# SensorShield.net
KiCad netlist of a schematic drawn in Altium Designer
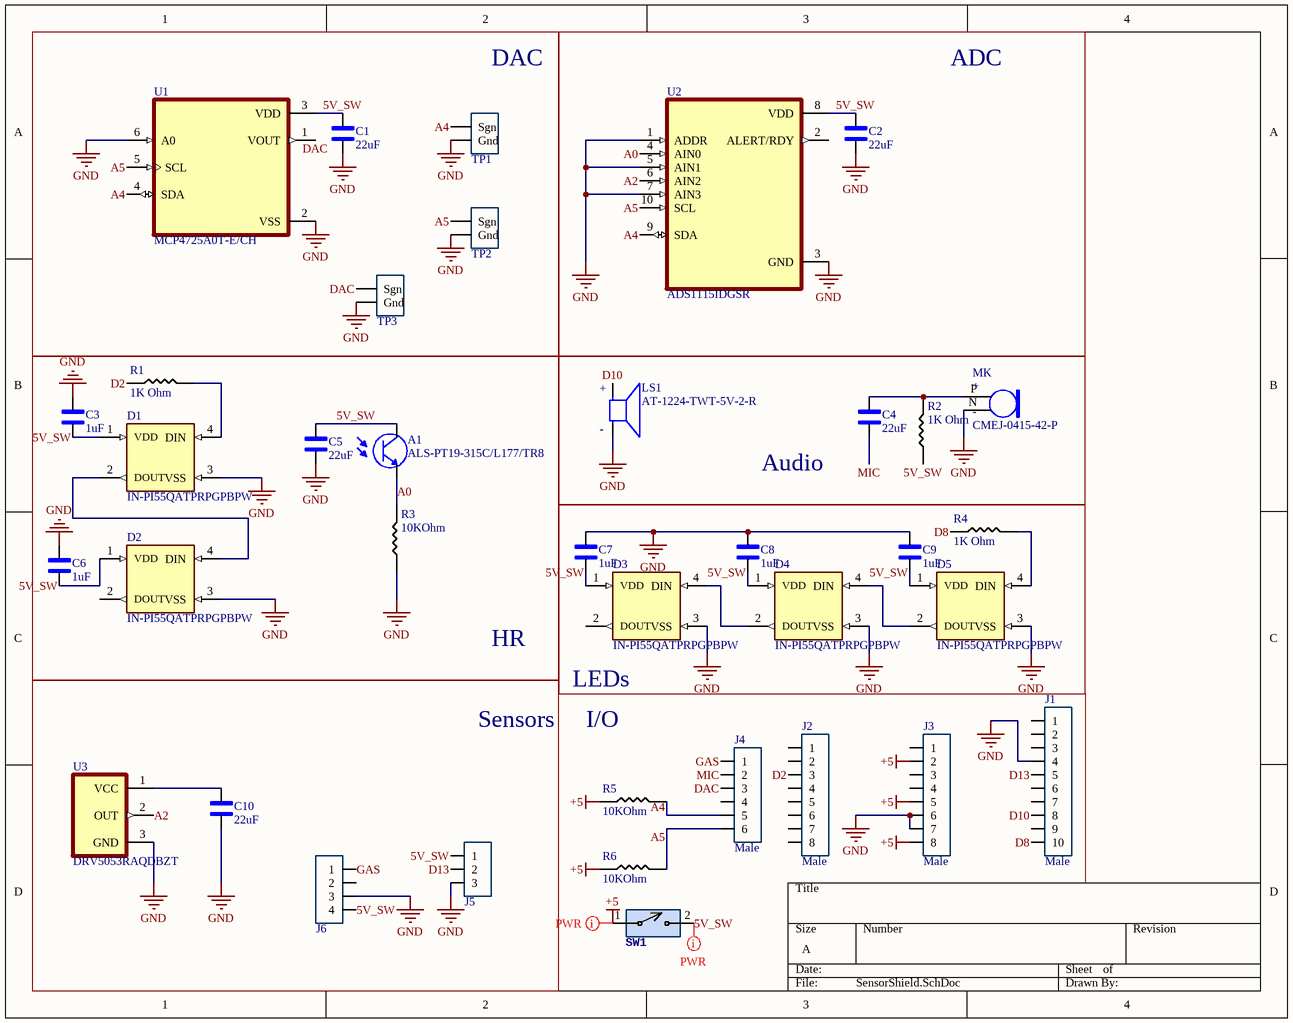
[diagram p0: SensorShield.SchDoc]

(export (version "E")
  (design (tool "Eeschema 10.0.6"))
  (components
    (comp (ref "A1")
      (value "ALS-PT19-315C/L177/TR8")
      (footprint "XDCR_ALS-PT19-315C/L177/TR8")
      (description "Phototransistors 630nm 2-SMD, No Lead")
      (fields (field (name "MF") "Everlight"))
      (libsource (lib "SensorShield") (part "ALS-PT19-315C/L177/TR8"))
    )
    (comp (ref "C1")
      (value "22uF")
      (footprint "1206_Passive_Capacitor")
      (description "22µF ±20% 16V Ceramic Capacitor X5R 1206 (3216 Metric)")
      (fields (field (name "DIGIKEY PART") "1276-2728-1-ND") (field (name "MFR PART #") "CL31A226KPHNNNE"))
      (libsource (lib "ECEN5730Lib_Manual_2021_08") (part "C_22uF_1206"))
    )
    (comp (ref "C2")
      (value "22uF")
      (footprint "1206_Passive_Capacitor")
      (description "22µF ±20% 16V Ceramic Capacitor X5R 1206 (3216 Metric)")
      (fields (field (name "DIGIKEY PART") "1276-2728-1-ND") (field (name "MFR PART #") "CL31A226KPHNNNE"))
      (libsource (lib "ECEN5730Lib_Manual_2021_08") (part "C_22uF_1206"))
    )
    (comp (ref "C3")
      (value "1uF")
      (footprint "1206_Passive_Capacitor")
      (description "1µF ±20% 16V Ceramic Capacitor X7R 1206 (3216 Metric)")
      (fields (field (name "DIGIKEY PART") "399-8150-1-ND") (field (name "MFR PART #") "CL31B105KBHNNNE"))
      (libsource (lib "ECEN5730Lib_Manual_2021_08") (part "C_1uF_1206"))
    )
    (comp (ref "C4")
      (value "22uF")
      (footprint "1206_Passive_Capacitor")
      (description "22µF ±20% 16V Ceramic Capacitor X5R 1206 (3216 Metric)")
      (fields (field (name "DIGIKEY PART") "1276-2728-1-ND") (field (name "MFR PART #") "CL31A226KPHNNNE"))
      (libsource (lib "ECEN5730Lib_Manual_2021_08") (part "C_22uF_1206"))
    )
    (comp (ref "C5")
      (value "22uF")
      (footprint "1206_Passive_Capacitor")
      (description "22µF ±20% 16V Ceramic Capacitor X5R 1206 (3216 Metric)")
      (fields (field (name "DIGIKEY PART") "1276-2728-1-ND") (field (name "MFR PART #") "CL31A226KPHNNNE"))
      (libsource (lib "ECEN5730Lib_Manual_2021_08") (part "C_22uF_1206"))
    )
    (comp (ref "C6")
      (value "1uF")
      (footprint "1206_Passive_Capacitor")
      (description "1µF ±20% 16V Ceramic Capacitor X7R 1206 (3216 Metric)")
      (fields (field (name "DIGIKEY PART") "399-8150-1-ND") (field (name "MFR PART #") "CL31B105KBHNNNE"))
      (libsource (lib "ECEN5730Lib_Manual_2021_08") (part "C_1uF_1206"))
    )
    (comp (ref "C7")
      (value "1uF")
      (footprint "1206_Passive_Capacitor")
      (description "1µF ±20% 16V Ceramic Capacitor X7R 1206 (3216 Metric)")
      (fields (field (name "DIGIKEY PART") "399-8150-1-ND") (field (name "MFR PART #") "CL31B105KBHNNNE"))
      (libsource (lib "ECEN5730Lib_Manual_2021_08") (part "C_1uF_1206"))
    )
    (comp (ref "C8")
      (value "1uF")
      (footprint "1206_Passive_Capacitor")
      (description "1µF ±20% 16V Ceramic Capacitor X7R 1206 (3216 Metric)")
      (fields (field (name "DIGIKEY PART") "399-8150-1-ND") (field (name "MFR PART #") "CL31B105KBHNNNE"))
      (libsource (lib "ECEN5730Lib_Manual_2021_08") (part "C_1uF_1206"))
    )
    (comp (ref "C9")
      (value "1uF")
      (footprint "1206_Passive_Capacitor")
      (description "1µF ±20% 16V Ceramic Capacitor X7R 1206 (3216 Metric)")
      (fields (field (name "DIGIKEY PART") "399-8150-1-ND") (field (name "MFR PART #") "CL31B105KBHNNNE"))
      (libsource (lib "ECEN5730Lib_Manual_2021_08") (part "C_1uF_1206"))
    )
    (comp (ref "C10")
      (value "22uF")
      (footprint "1206_Passive_Capacitor")
      (description "22µF ±20% 16V Ceramic Capacitor X5R 1206 (3216 Metric)")
      (fields (field (name "DIGIKEY PART") "1276-2728-1-ND") (field (name "MFR PART #") "CL31A226KPHNNNE"))
      (libsource (lib "ECEN5730Lib_Manual_2021_08") (part "C_22uF_1206"))
    )
    (comp (ref "D1")
      (value "IN-PI55QATPRPGPBPW")
      (footprint "SERIAL_LED")
      (description "Digital Series Cascade LED")
      (libsource (lib "ECEN5730Lib_Manual_2021_08") (part "LED_Smart_5050"))
    )
    (comp (ref "D2")
      (value "IN-PI55QATPRPGPBPW")
      (footprint "SERIAL_LED")
      (description "Digital Series Cascade LED")
      (libsource (lib "ECEN5730Lib_Manual_2021_08") (part "LED_Smart_5050"))
    )
    (comp (ref "D3")
      (value "IN-PI55QATPRPGPBPW")
      (footprint "SERIAL_LED")
      (description "Digital Series Cascade LED")
      (libsource (lib "ECEN5730Lib_Manual_2021_08") (part "LED_Smart_5050"))
    )
    (comp (ref "D4")
      (value "IN-PI55QATPRPGPBPW")
      (footprint "SERIAL_LED")
      (description "Digital Series Cascade LED")
      (libsource (lib "ECEN5730Lib_Manual_2021_08") (part "LED_Smart_5050"))
    )
    (comp (ref "D5")
      (value "IN-PI55QATPRPGPBPW")
      (footprint "SERIAL_LED")
      (description "Digital Series Cascade LED")
      (libsource (lib "ECEN5730Lib_Manual_2021_08") (part "LED_Smart_5050"))
    )
    (comp (ref "J1")
      (value "Male")
      (footprint "10_PIN_100MIL")
      (description "10 Position Header Connector 0.100\" (2.54mm) Through Hole Tin")
      (fields (field (name "DIGIKEY PART") "S7008-ND") (field (name "LCSC PART#") "DNP"))
      (libsource (lib "ECEN5730Lib_Manual_2021_08") (part "JM_10_PIN_MALE"))
    )
    (comp (ref "J2")
      (value "Male")
      (footprint "8_PIN_100MIL")
      (description "8 Position Header Connector 0.100\" (2.54mm) Through Hole Tin")
      (fields (field (name "DIGIKEY PART") "S7006-ND") (field (name "LCSC PART#") "DNP"))
      (libsource (lib "ECEN5730Lib_Manual_2021_08") (part "JM_8_PIN_MALE"))
    )
    (comp (ref "J3")
      (value "Male")
      (footprint "8_PIN_100MIL")
      (description "8 Position Header Connector 0.100\" (2.54mm) Through Hole Tin")
      (fields (field (name "DIGIKEY PART") "S7006-ND") (field (name "LCSC PART#") "DNP"))
      (libsource (lib "ECEN5730Lib_Manual_2021_08") (part "JM_8_PIN_MALE"))
    )
    (comp (ref "J4")
      (value "Male")
      (footprint "6_PIN_100MIL")
      (description "6 Position Header Connector 0.100\" (2.54mm) Through Hole Tin")
      (fields (field (name "DIGIKEY PART") "S7004-ND") (field (name "LCSC PART#") "DNP"))
      (libsource (lib "ECEN5730Lib_Manual_2021_08") (part "JM_6_PIN_MALE"))
    )
    (comp (ref "J5")
      (value "J_3_PIN_HEADER")
      (footprint "3_PIN_100mil")
      (description "3 Position Header Connector 0.100\" (2.54mm) Through Hole Tin")
      (libsource (lib "ECEN5730Lib_Manual_2021_08") (part "J_3_PIN_HEADER"))
    )
    (comp (ref "J6")
      (value "J_4_PIN_HEADER")
      (footprint "4_PIN_100MIL")
      (description "4 Position Header Connector 0.100\" (2.54mm) Through Hole Tin")
      (libsource (lib "ECEN5730Lib_Manual_2021_08") (part "J_4_PIN_HEADER"))
    )
    (comp (ref "LS1")
      (value "AT-1224-TWT-5V-2-R")
      (footprint "XDCR_AT-1224-TWT-5V-2-R")
      (description "AUDIO TRANSDUCER 5 VP-P 87 DB 2400 HZ")
      (fields (field (name "MF") "PUI Audio,"))
      (libsource (lib "SensorShield") (part "AT-1224-TWT-5V-2-R"))
    )
    (comp (ref "MK")
      (value "CMEJ-0415-42-P")
      (footprint "MIC_CMEJ-0415-42-P")
      (fields (field (name "MF") "CUI Devices") (field (name "DIGI-KEY_PART_NUMBER") "102-6542-ND"))
      (libsource (lib "SensorShield") (part "CMEJ-0415-42-P"))
    )
    (comp (ref "R1")
      (value "1K Ohm")
      (footprint "1206_Passive_Resitor")
      (description "1 kOhms ±1% 0.5W, 1/2W Chip Resistor 1206 (3216 Metric) Anti-Sulfur, Moisture Resistant Thin Film")
      (fields
        (field (name "DIGIKEY PART") "RNCP1206FTD1K00CT-ND")
        (field (name "MFR PART #") "1206W4F1001T5")
      )
      (libsource (lib "ECEN5730Lib_Manual_2021_08") (part "R_1K_1206"))
    )
    (comp (ref "R2")
      (value "1K Ohm")
      (footprint "1206_Passive_Resitor")
      (description "1 kOhms ±1% 0.5W, 1/2W Chip Resistor 1206 (3216 Metric) Anti-Sulfur, Moisture Resistant Thin Film")
      (fields
        (field (name "DIGIKEY PART") "RNCP1206FTD1K00CT-ND")
        (field (name "MFR PART #") "1206W4F1001T5")
      )
      (libsource (lib "ECEN5730Lib_Manual_2021_08") (part "R_1K_1206"))
    )
    (comp (ref "R3")
      (value "10KOhm")
      (footprint "1206_Passive_Resitor")
      (description "10 kOhms ±5% 0.25W, 1/4W Chip Resistor 1206 (3216 Metric) Automotive AEC-Q200 Thick Film")
      (fields (field (name "DIGIKEY PART") "RMCF1206JT300RCT-ND") (field (name "Comment") "10k"))
      (libsource (lib "ECEN5730Lib_Manual_2021_08") (part "R_10KOhm_1206"))
    )
    (comp (ref "R4")
      (value "1K Ohm")
      (footprint "1206_Passive_Resitor")
      (description "1 kOhms ±1% 0.5W, 1/2W Chip Resistor 1206 (3216 Metric) Anti-Sulfur, Moisture Resistant Thin Film")
      (fields
        (field (name "DIGIKEY PART") "RNCP1206FTD1K00CT-ND")
        (field (name "MFR PART #") "1206W4F1001T5")
      )
      (libsource (lib "ECEN5730Lib_Manual_2021_08") (part "R_1K_1206"))
    )
    (comp (ref "R5")
      (value "10KOhm")
      (footprint "1206_Passive_Resitor")
      (description "10 kOhms ±5% 0.25W, 1/4W Chip Resistor 1206 (3216 Metric) Automotive AEC-Q200 Thick Film")
      (fields (field (name "DIGIKEY PART") "RMCF1206JT300RCT-ND") (field (name "Comment") "10k"))
      (libsource (lib "ECEN5730Lib_Manual_2021_08") (part "R_10KOhm_1206"))
    )
    (comp (ref "R6")
      (value "10KOhm")
      (footprint "1206_Passive_Resitor")
      (description "10 kOhms ±5% 0.25W, 1/4W Chip Resistor 1206 (3216 Metric) Automotive AEC-Q200 Thick Film")
      (fields (field (name "DIGIKEY PART") "RMCF1206JT300RCT-ND") (field (name "Comment") "10k"))
      (libsource (lib "ECEN5730Lib_Manual_2021_08") (part "R_10KOhm_1206"))
    )
    (comp (ref "SW1")
      (value "SW_2Pin_100mil_Switch")
      (footprint "2Pin-Header-Conn")
      (description "2Pin Header")
      (fields (field (name "LCSC PART#") "C124375"))
      (libsource (lib "ECEN5730Lib_JLC_2021_08") (part "SW_2Pin_100mil_Switch"))
    )
    (comp (ref "TP1")
      (value "10x Probe TP")
      (footprint "TP10x_Probe")
      (description "Test Point 300 mil centers")
      (libsource (lib "ECEN5730Lib_Manual_2021_08") (part "TP_10x_Probe"))
    )
    (comp (ref "TP2")
      (value "10x Probe TP")
      (footprint "TP10x_Probe")
      (description "Test Point 300 mil centers")
      (libsource (lib "ECEN5730Lib_Manual_2021_08") (part "TP_10x_Probe"))
    )
    (comp (ref "TP3")
      (value "10x Probe TP")
      (footprint "TP10x_Probe")
      (description "Test Point 300 mil centers")
      (libsource (lib "ECEN5730Lib_Manual_2021_08") (part "TP_10x_Probe"))
    )
    (comp (ref "U1")
      (value "MCP4725A0T-E/CH")
      (footprint "SOT95P270X145-6N")
      (description "12 Bit Digital to Analog Converter 1 SOT-23-6")
      (fields (field (name "MF") "Microchip"))
      (libsource (lib "SensorShield") (part "MCP4725A0T-E/CH"))
    )
    (comp (ref "U2")
      (value "ADS1115IDGSR")
      (footprint "SOP50P490X110-10N")
      (fields
        (field (name "MF") "Texas Instruments")
        (field (name "BUYPART") "https://www.snapeda.com/parts/ADS1115IDGSR/Texas%20Instruments/view-part/45903/?ref=eda")
      )
      (libsource (lib "SensorShield") (part "ADS1115IDGSR"))
    )
    (comp (ref "U3")
      (value "DRV5053RAQDBZT")
      (footprint "SOT95P237X112-3N")
      (description "SENSOR LINEAR ANALOG SOT23-3")
      (libsource (lib "SensorShield") (part "DRV5053RAQDBZT"))
    )
  )
  (nets
    (net (code "1") (name "+5") (class "Default")
      (node (ref "J3") (pin "2") (pinfunction "2_2") (pintype "passive"))
      (node (ref "J3") (pin "5") (pinfunction "5_5") (pintype "passive"))
      (node (ref "J3") (pin "8") (pinfunction "8_8") (pintype "passive"))
      (node (ref "R5") (pin "1") (pinfunction "1_1") (pintype "passive"))
      (node (ref "R6") (pin "1") (pinfunction "1_1") (pintype "passive"))
      (node (ref "SW1") (pin "1") (pinfunction "1_1") (pintype "passive"))
    )
    (net (code "2") (name "/5V_SW") (class "Default")
      (node (ref "A1") (pin "1") (pinfunction "C_1") (pintype "passive"))
      (node (ref "C1") (pin "2") (pinfunction "2_2") (pintype "passive"))
      (node (ref "C2") (pin "2") (pinfunction "2_2") (pintype "passive"))
      (node (ref "C3") (pin "1") (pinfunction "1_1") (pintype "passive"))
      (node (ref "C5") (pin "2") (pinfunction "2_2") (pintype "passive"))
      (node (ref "C6") (pin "1") (pinfunction "1_1") (pintype "passive"))
      (node (ref "C7") (pin "1") (pinfunction "1_1") (pintype "passive"))
      (node (ref "C8") (pin "1") (pinfunction "1_1") (pintype "passive"))
      (node (ref "C9") (pin "1") (pinfunction "1_1") (pintype "passive"))
      (node (ref "D1") (pin "1") (pinfunction "VDD_1") (pintype "input"))
      (node (ref "D2") (pin "1") (pinfunction "VDD_1") (pintype "input"))
      (node (ref "D3") (pin "1") (pinfunction "VDD_1") (pintype "input"))
      (node (ref "D4") (pin "1") (pinfunction "VDD_1") (pintype "input"))
      (node (ref "D5") (pin "1") (pinfunction "VDD_1") (pintype "input"))
      (node (ref "J5") (pin "1") (pinfunction "1_1") (pintype "passive"))
      (node (ref "J6") (pin "4") (pinfunction "4_4") (pintype "passive"))
      (node (ref "R2") (pin "1") (pinfunction "1_1") (pintype "passive"))
      (node (ref "SW1") (pin "2") (pinfunction "2_2") (pintype "passive"))
      (node (ref "U1") (pin "3") (pinfunction "VDD_3") (pintype "power_in"))
      (node (ref "U2") (pin "8") (pinfunction "VDD_8") (pintype "power_in"))
    )
    (net (code "3") (name "/A0") (class "Default")
      (node (ref "A1") (pin "2") (pinfunction "E_2") (pintype "passive"))
      (node (ref "R3") (pin "2") (pinfunction "2_2") (pintype "passive"))
      (node (ref "U2") (pin "4") (pinfunction "AIN0_4") (pintype "input"))
    )
    (net (code "4") (name "/A2") (class "Default")
      (node (ref "U2") (pin "6") (pinfunction "AIN2_6") (pintype "input"))
      (node (ref "U3") (pin "2") (pinfunction "OUT_2") (pintype "output"))
    )
    (net (code "5") (name "/A4") (class "Default")
      (node (ref "J4") (pin "5") (pinfunction "5_5") (pintype "passive"))
      (node (ref "R5") (pin "2") (pinfunction "2_2") (pintype "passive"))
      (node (ref "TP1") (pin "1") (pinfunction "Sgn_1") (pintype "passive"))
      (node (ref "U1") (pin "4") (pinfunction "SDA_4") (pintype "bidirectional"))
      (node (ref "U2") (pin "9") (pinfunction "SDA_9") (pintype "bidirectional"))
    )
    (net (code "6") (name "/A5") (class "Default")
      (node (ref "J4") (pin "6") (pinfunction "6_6") (pintype "passive"))
      (node (ref "R6") (pin "2") (pinfunction "2_2") (pintype "passive"))
      (node (ref "TP2") (pin "1") (pinfunction "Sgn_1") (pintype "passive"))
      (node (ref "U1") (pin "5") (pinfunction "SCL_5") (pintype "input"))
      (node (ref "U2") (pin "10") (pinfunction "SCL_10") (pintype "input"))
    )
    (net (code "7") (name "/D2") (class "Default")
      (node (ref "J2") (pin "3") (pinfunction "3_3") (pintype "passive"))
      (node (ref "R1") (pin "1") (pinfunction "1_1") (pintype "passive"))
    )
    (net (code "8") (name "/D8") (class "Default")
      (node (ref "J1") (pin "10") (pinfunction "10_10") (pintype "passive"))
      (node (ref "R4") (pin "1") (pinfunction "1_1") (pintype "passive"))
    )
    (net (code "9") (name "/D10") (class "Default")
      (node (ref "J1") (pin "8") (pinfunction "8_8") (pintype "passive"))
      (node (ref "LS1") (pin "P") (pinfunction "P_P") (pintype "passive"))
    )
    (net (code "10") (name "/D13") (class "Default")
      (node (ref "J1") (pin "5") (pinfunction "5_5") (pintype "passive"))
      (node (ref "J5") (pin "2") (pinfunction "2_2") (pintype "passive"))
    )
    (net (code "11") (name "/DAC") (class "Default")
      (node (ref "J4") (pin "3") (pinfunction "3_3") (pintype "passive"))
      (node (ref "TP3") (pin "1") (pinfunction "Sgn_1") (pintype "passive"))
      (node (ref "U1") (pin "1") (pinfunction "VOUT_1") (pintype "output"))
    )
    (net (code "12") (name "/GAS") (class "Default")
      (node (ref "J4") (pin "1") (pinfunction "1_1") (pintype "passive"))
      (node (ref "J6") (pin "1") (pinfunction "1_1") (pintype "passive"))
    )
    (net (code "13") (name "/MIC") (class "Default")
      (node (ref "C4") (pin "1") (pinfunction "1_1") (pintype "passive"))
      (node (ref "J4") (pin "2") (pinfunction "2_2") (pintype "passive"))
    )
    (net (code "14") (name "GND") (class "Default")
      (node (ref "C1") (pin "1") (pinfunction "1_1") (pintype "passive"))
      (node (ref "C10") (pin "1") (pinfunction "1_1") (pintype "passive"))
      (node (ref "C2") (pin "1") (pinfunction "1_1") (pintype "passive"))
      (node (ref "C3") (pin "2") (pinfunction "2_2") (pintype "passive"))
      (node (ref "C5") (pin "1") (pinfunction "1_1") (pintype "passive"))
      (node (ref "C6") (pin "2") (pinfunction "2_2") (pintype "passive"))
      (node (ref "C7") (pin "2") (pinfunction "2_2") (pintype "passive"))
      (node (ref "C8") (pin "2") (pinfunction "2_2") (pintype "passive"))
      (node (ref "C9") (pin "2") (pinfunction "2_2") (pintype "passive"))
      (node (ref "D1") (pin "3") (pinfunction "VSS_3") (pintype "input"))
      (node (ref "D2") (pin "3") (pinfunction "VSS_3") (pintype "input"))
      (node (ref "D3") (pin "3") (pinfunction "VSS_3") (pintype "input"))
      (node (ref "D4") (pin "3") (pinfunction "VSS_3") (pintype "input"))
      (node (ref "D5") (pin "3") (pinfunction "VSS_3") (pintype "input"))
      (node (ref "J1") (pin "4") (pinfunction "4_4") (pintype "passive"))
      (node (ref "J3") (pin "6") (pinfunction "6_6") (pintype "passive"))
      (node (ref "J3") (pin "7") (pinfunction "7_7") (pintype "passive"))
      (node (ref "J5") (pin "3") (pinfunction "3_3") (pintype "passive"))
      (node (ref "J6") (pin "3") (pinfunction "3_3") (pintype "passive"))
      (node (ref "LS1") (pin "N") (pinfunction "N_N") (pintype "passive"))
      (node (ref "MK") (pin "N") (pinfunction "GND_N") (pintype "passive"))
      (node (ref "R3") (pin "1") (pinfunction "1_1") (pintype "passive"))
      (node (ref "TP1") (pin "2") (pinfunction "Gnd_2") (pintype "passive"))
      (node (ref "TP2") (pin "2") (pinfunction "Gnd_2") (pintype "passive"))
      (node (ref "TP3") (pin "2") (pinfunction "Gnd_2") (pintype "passive"))
      (node (ref "U1") (pin "2") (pinfunction "VSS_2") (pintype "power_in"))
      (node (ref "U1") (pin "6") (pinfunction "A0_6") (pintype "input"))
      (node (ref "U2") (pin "1") (pinfunction "ADDR_1") (pintype "input"))
      (node (ref "U2") (pin "3") (pinfunction "GND_3") (pintype "power_in"))
      (node (ref "U2") (pin "5") (pinfunction "AIN1_5") (pintype "input"))
      (node (ref "U2") (pin "7") (pinfunction "AIN3_7") (pintype "input"))
      (node (ref "U3") (pin "3") (pinfunction "GND_3") (pintype "power_in"))
    )
    (net (code "15") (name "Net-(D1-DIN)") (class "Default")
      (node (ref "D1") (pin "4") (pinfunction "DIN_4") (pintype "input"))
      (node (ref "R1") (pin "2") (pinfunction "2_2") (pintype "passive"))
    )
    (net (code "16") (name "Net-(D1-DOUT)") (class "Default")
      (node (ref "D1") (pin "2") (pinfunction "DOUT_2") (pintype "output"))
      (node (ref "D2") (pin "4") (pinfunction "DIN_4") (pintype "input"))
    )
    (net (code "17") (name "Net-(D3-DIN)") (class "Default")
      (node (ref "D3") (pin "4") (pinfunction "DIN_4") (pintype "input"))
      (node (ref "D4") (pin "2") (pinfunction "DOUT_2") (pintype "output"))
    )
    (net (code "18") (name "Net-(D4-DIN)") (class "Default")
      (node (ref "D4") (pin "4") (pinfunction "DIN_4") (pintype "input"))
      (node (ref "D5") (pin "2") (pinfunction "DOUT_2") (pintype "output"))
    )
    (net (code "19") (name "Net-(D5-DIN)") (class "Default")
      (node (ref "D5") (pin "4") (pinfunction "DIN_4") (pintype "input"))
      (node (ref "R4") (pin "2") (pinfunction "2_2") (pintype "passive"))
    )
    (net (code "20") (name "Net-(MK-OUTPUT)") (class "Default")
      (node (ref "C4") (pin "2") (pinfunction "2_2") (pintype "passive"))
      (node (ref "MK") (pin "P") (pinfunction "OUTPUT_P") (pintype "passive"))
      (node (ref "R2") (pin "2") (pinfunction "2_2") (pintype "passive"))
    )
    (net (code "21") (name "Net-(U3-VCC)") (class "Default")
      (node (ref "C10") (pin "2") (pinfunction "2_2") (pintype "passive"))
      (node (ref "U3") (pin "1") (pinfunction "VCC_1") (pintype "power_in"))
    )
    (net (code "22") (name "unconnected-(D2-DOUT-Pad2)") (class "Default")
      (node (ref "D2") (pin "2") (pinfunction "DOUT_2") (pintype "output"))
    )
    (net (code "23") (name "unconnected-(D3-DOUT-Pad2)") (class "Default")
      (node (ref "D3") (pin "2") (pinfunction "DOUT_2") (pintype "output"))
    )
    (net (code "24") (name "unconnected-(J1-Pad1)") (class "Default")
      (node (ref "J1") (pin "1") (pinfunction "1_1") (pintype "passive"))
    )
    (net (code "25") (name "unconnected-(J1-Pad2)") (class "Default")
      (node (ref "J1") (pin "2") (pinfunction "2_2") (pintype "passive"))
    )
    (net (code "26") (name "unconnected-(J1-Pad3)") (class "Default")
      (node (ref "J1") (pin "3") (pinfunction "3_3") (pintype "passive"))
    )
    (net (code "27") (name "unconnected-(J1-Pad6)") (class "Default")
      (node (ref "J1") (pin "6") (pinfunction "6_6") (pintype "passive"))
    )
    (net (code "28") (name "unconnected-(J1-Pad7)") (class "Default")
      (node (ref "J1") (pin "7") (pinfunction "7_7") (pintype "passive"))
    )
    (net (code "29") (name "unconnected-(J1-Pad9)") (class "Default")
      (node (ref "J1") (pin "9") (pinfunction "9_9") (pintype "passive"))
    )
    (net (code "30") (name "unconnected-(J2-Pad1)") (class "Default")
      (node (ref "J2") (pin "1") (pinfunction "1_1") (pintype "passive"))
    )
    (net (code "31") (name "unconnected-(J2-Pad2)") (class "Default")
      (node (ref "J2") (pin "2") (pinfunction "2_2") (pintype "passive"))
    )
    (net (code "32") (name "unconnected-(J2-Pad4)") (class "Default")
      (node (ref "J2") (pin "4") (pinfunction "4_4") (pintype "passive"))
    )
    (net (code "33") (name "unconnected-(J2-Pad5)") (class "Default")
      (node (ref "J2") (pin "5") (pinfunction "5_5") (pintype "passive"))
    )
    (net (code "34") (name "unconnected-(J2-Pad6)") (class "Default")
      (node (ref "J2") (pin "6") (pinfunction "6_6") (pintype "passive"))
    )
    (net (code "35") (name "unconnected-(J2-Pad7)") (class "Default")
      (node (ref "J2") (pin "7") (pinfunction "7_7") (pintype "passive"))
    )
    (net (code "36") (name "unconnected-(J2-Pad8)") (class "Default")
      (node (ref "J2") (pin "8") (pinfunction "8_8") (pintype "passive"))
    )
    (net (code "37") (name "unconnected-(J3-Pad1)") (class "Default")
      (node (ref "J3") (pin "1") (pinfunction "1_1") (pintype "passive"))
    )
    (net (code "38") (name "unconnected-(J3-Pad3)") (class "Default")
      (node (ref "J3") (pin "3") (pinfunction "3_3") (pintype "passive"))
    )
    (net (code "39") (name "unconnected-(J3-Pad4)") (class "Default")
      (node (ref "J3") (pin "4") (pinfunction "4_4") (pintype "passive"))
    )
    (net (code "40") (name "unconnected-(J4-Pad4)") (class "Default")
      (node (ref "J4") (pin "4") (pinfunction "4_4") (pintype "passive"))
    )
    (net (code "41") (name "unconnected-(J6-Pad2)") (class "Default")
      (node (ref "J6") (pin "2") (pinfunction "2_2") (pintype "passive"))
    )
    (net (code "42") (name "unconnected-(U2-ALERT{slash}RDY-Pad2)") (class "Default")
      (node (ref "U2") (pin "2") (pinfunction "ALERT/RDY_2") (pintype "output"))
    )
  )
)
